# ESP8266_MegaD_top_board.net
KiCad netlist of a schematic drawn in EAGLE
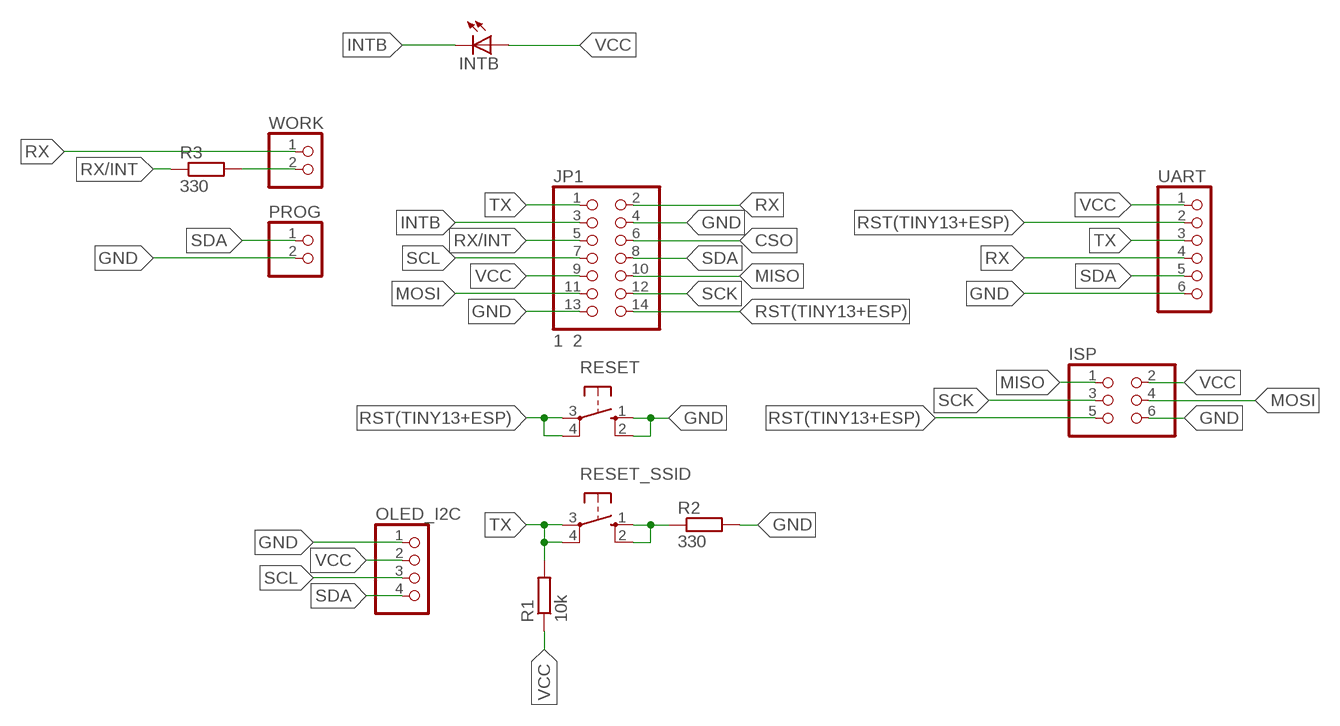
[diagram p0: schematic, sheet 1]

(export (version "E")
  (design (tool "Eeschema 10.0.6"))
  (components
    (comp (ref "INTB")
      (value "LED3MM")
      (footprint "eagle-import:LED3MM")
      (libsource (lib "eagle-import") (part "LED3MM"))
    )
    (comp (ref "ISP")
      (value "PINHD-2X3")
      (footprint "eagle-import:2X03")
      (libsource (lib "eagle-import") (part "PINHD-2X3"))
    )
    (comp (ref "JP1")
      (value "1 2")
      (footprint "eagle-import:2X07")
      (libsource (lib "eagle-import") (part "PINHD-2X7"))
    )
    (comp (ref "OLED_I2C")
      (value "PINHD-1X4")
      (footprint "eagle-import:1X04")
      (libsource (lib "eagle-import") (part "PINHD-1X4"))
    )
    (comp (ref "PROG")
      (value "PINHD-1X2/90")
      (footprint "eagle-import:1X02_90")
      (libsource (lib "eagle-import") (part "PINHD-1X2/90"))
    )
    (comp (ref "R1")
      (value "10k")
      (footprint "eagle-import:R1206")
      (libsource (lib "eagle-import") (part "R-EU_R1206"))
    )
    (comp (ref "R2")
      (value "330")
      (footprint "eagle-import:R1206")
      (libsource (lib "eagle-import") (part "R-EU_R1206"))
    )
    (comp (ref "R3")
      (value "330")
      (footprint "eagle-import:R1206")
      (libsource (lib "eagle-import") (part "R-EU_R1206"))
    )
    (comp (ref "RESET")
      (value "10-XX")
      (footprint "eagle-import:B3F-10XX")
      (fields (field (name "MPN") "B3F-1000"))
      (libsource (lib "eagle-import") (part "10-XX"))
    )
    (comp (ref "RESET_SSID")
      (value "10-XX")
      (footprint "eagle-import:B3F-10XX")
      (fields (field (name "MPN") "B3F-1000"))
      (libsource (lib "eagle-import") (part "10-XX"))
    )
    (comp (ref "UART")
      (value "PINHD-1X6")
      (footprint "eagle-import:1X06")
      (libsource (lib "eagle-import") (part "PINHD-1X6"))
    )
    (comp (ref "WORK")
      (value "PINHD-1X2/90")
      (footprint "eagle-import:1X02_90")
      (libsource (lib "eagle-import") (part "PINHD-1X2/90"))
    )
  )
  (nets
    (net (code "1") (name "CSO") (class "Default")
      (node (ref "JP1") (pin "6") (pinfunction "6_6") (pintype "passive"))
    )
    (net (code "2") (name "GND") (class "Default")
      (node (ref "ISP") (pin "6") (pinfunction "6_6") (pintype "passive"))
      (node (ref "JP1") (pin "13") (pinfunction "13_13") (pintype "passive"))
      (node (ref "JP1") (pin "4") (pinfunction "4_4") (pintype "passive"))
      (node (ref "OLED_I2C") (pin "1") (pinfunction "1_1") (pintype "passive"))
      (node (ref "PROG") (pin "2") (pinfunction "2_2") (pintype "passive"))
      (node (ref "R2") (pin "2") (pinfunction "2_2") (pintype "passive"))
      (node (ref "RESET") (pin "1") (pinfunction "S_1") (pintype "passive"))
      (node (ref "RESET") (pin "2") (pinfunction "S1_2") (pintype "passive"))
      (node (ref "UART") (pin "6") (pinfunction "6_6") (pintype "passive"))
    )
    (net (code "3") (name "INTB") (class "Default")
      (node (ref "INTB") (pin "K") (pinfunction "C_K") (pintype "passive"))
      (node (ref "JP1") (pin "3") (pinfunction "3_3") (pintype "passive"))
    )
    (net (code "4") (name "MISO") (class "Default")
      (node (ref "ISP") (pin "1") (pinfunction "1_1") (pintype "passive"))
      (node (ref "JP1") (pin "10") (pinfunction "10_10") (pintype "passive"))
    )
    (net (code "5") (name "MOSI") (class "Default")
      (node (ref "ISP") (pin "4") (pinfunction "4_4") (pintype "passive"))
      (node (ref "JP1") (pin "11") (pinfunction "11_11") (pintype "passive"))
    )
    (net (code "6") (name "Net-(R3-Pad2)") (class "Default")
      (node (ref "R3") (pin "2") (pinfunction "2_2") (pintype "passive"))
      (node (ref "WORK") (pin "2") (pinfunction "2_2") (pintype "passive"))
    )
    (net (code "7") (name "Net-(RESET_SSID-S)") (class "Default")
      (node (ref "R2") (pin "1") (pinfunction "1_1") (pintype "passive"))
      (node (ref "RESET_SSID") (pin "1") (pinfunction "S_1") (pintype "passive"))
      (node (ref "RESET_SSID") (pin "2") (pinfunction "S1_2") (pintype "passive"))
    )
    (net (code "8") (name "RST(TINY13+ESP)") (class "Default")
      (node (ref "ISP") (pin "5") (pinfunction "5_5") (pintype "passive"))
      (node (ref "JP1") (pin "14") (pinfunction "14_14") (pintype "passive"))
      (node (ref "RESET") (pin "3") (pinfunction "P_3") (pintype "passive"))
      (node (ref "RESET") (pin "4") (pinfunction "P1_4") (pintype "passive"))
      (node (ref "UART") (pin "2") (pinfunction "2_2") (pintype "passive"))
    )
    (net (code "9") (name "RX") (class "Default")
      (node (ref "JP1") (pin "2") (pinfunction "2_2") (pintype "passive"))
      (node (ref "UART") (pin "4") (pinfunction "4_4") (pintype "passive"))
      (node (ref "WORK") (pin "1") (pinfunction "1_1") (pintype "passive"))
    )
    (net (code "10") (name "RX{slash}INT") (class "Default")
      (node (ref "JP1") (pin "5") (pinfunction "5_5") (pintype "passive"))
      (node (ref "R3") (pin "1") (pinfunction "1_1") (pintype "passive"))
    )
    (net (code "11") (name "SCK") (class "Default")
      (node (ref "ISP") (pin "3") (pinfunction "3_3") (pintype "passive"))
      (node (ref "JP1") (pin "12") (pinfunction "12_12") (pintype "passive"))
    )
    (net (code "12") (name "SCL") (class "Default")
      (node (ref "JP1") (pin "7") (pinfunction "7_7") (pintype "passive"))
      (node (ref "OLED_I2C") (pin "3") (pinfunction "3_3") (pintype "passive"))
    )
    (net (code "13") (name "SDA") (class "Default")
      (node (ref "JP1") (pin "8") (pinfunction "8_8") (pintype "passive"))
      (node (ref "OLED_I2C") (pin "4") (pinfunction "4_4") (pintype "passive"))
      (node (ref "PROG") (pin "1") (pinfunction "1_1") (pintype "passive"))
      (node (ref "UART") (pin "5") (pinfunction "5_5") (pintype "passive"))
    )
    (net (code "14") (name "TX") (class "Default")
      (node (ref "JP1") (pin "1") (pinfunction "1_1") (pintype "passive"))
      (node (ref "R1") (pin "2") (pinfunction "2_2") (pintype "passive"))
      (node (ref "RESET_SSID") (pin "3") (pinfunction "P_3") (pintype "passive"))
      (node (ref "RESET_SSID") (pin "4") (pinfunction "P1_4") (pintype "passive"))
      (node (ref "UART") (pin "3") (pinfunction "3_3") (pintype "passive"))
    )
    (net (code "15") (name "VCC") (class "Default")
      (node (ref "INTB") (pin "A") (pinfunction "A_A") (pintype "passive"))
      (node (ref "ISP") (pin "2") (pinfunction "2_2") (pintype "passive"))
      (node (ref "JP1") (pin "9") (pinfunction "9_9") (pintype "passive"))
      (node (ref "OLED_I2C") (pin "2") (pinfunction "2_2") (pintype "passive"))
      (node (ref "R1") (pin "1") (pinfunction "1_1") (pintype "passive"))
      (node (ref "UART") (pin "1") (pinfunction "1_1") (pintype "passive"))
    )
  )
)
